# dualPilot.net
KiCad netlist of a schematic drawn in EAGLE
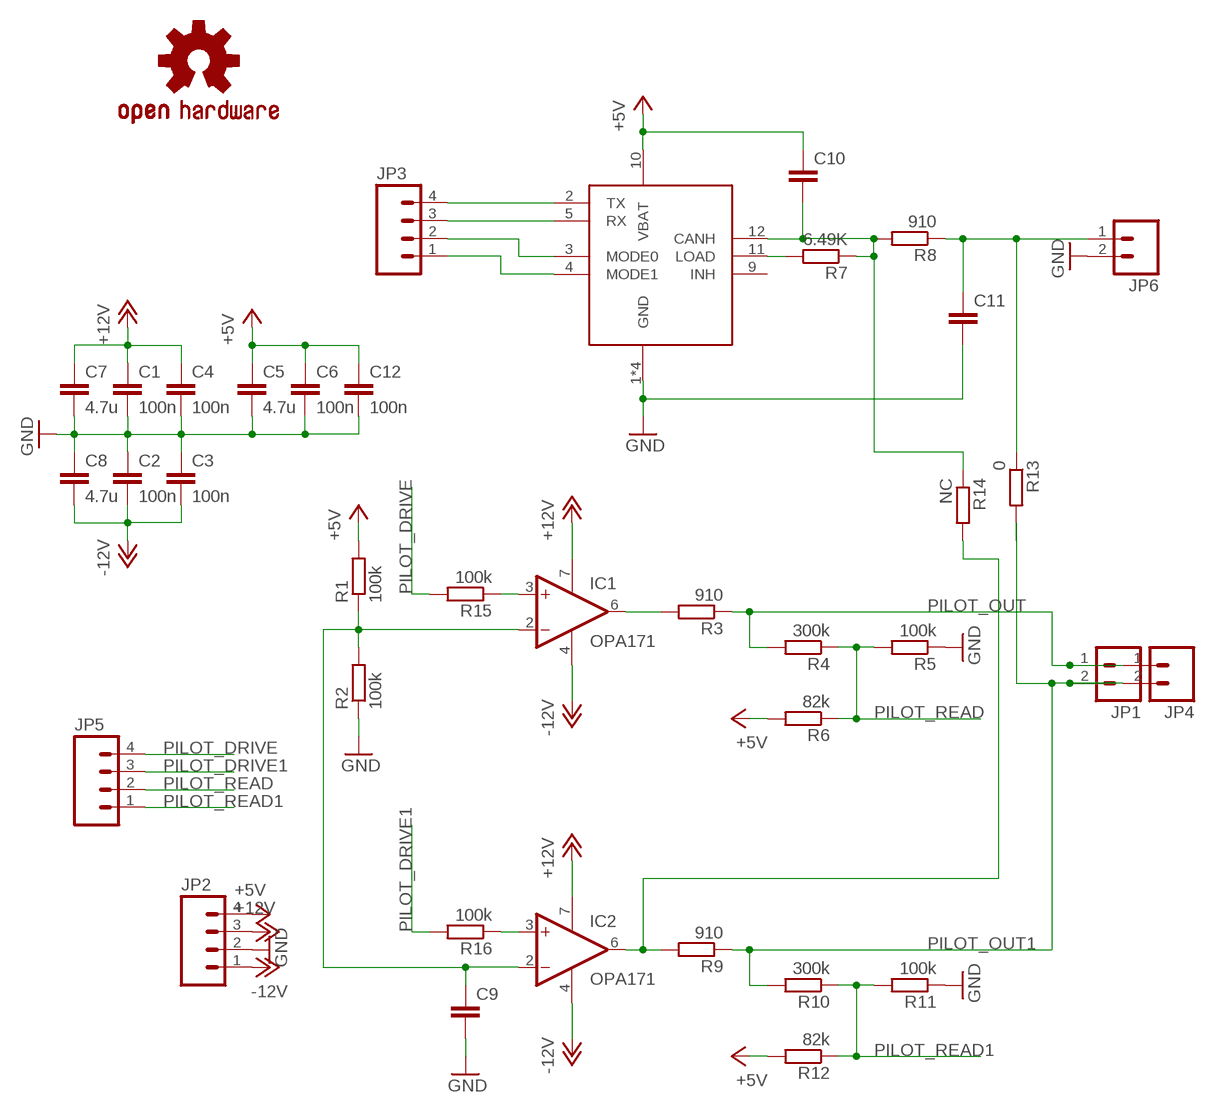
[diagram p0: schematic, sheet 1]

(export (version "E")
  (design (tool "Eeschema 10.0.6"))
  (components
    (comp (ref "C1")
      (value "100n")
      (footprint "eagle-import:0805")
      (libsource (lib "eagle-import") (part "CAP0805"))
    )
    (comp (ref "C2")
      (value "100n")
      (footprint "eagle-import:0805")
      (libsource (lib "eagle-import") (part "CAP0805"))
    )
    (comp (ref "C3")
      (value "100n")
      (footprint "eagle-import:0805")
      (libsource (lib "eagle-import") (part "CAP0805"))
    )
    (comp (ref "C4")
      (value "100n")
      (footprint "eagle-import:0805")
      (libsource (lib "eagle-import") (part "CAP0805"))
    )
    (comp (ref "C5")
      (value "4.7u")
      (footprint "eagle-import:0805")
      (libsource (lib "eagle-import") (part "CAP0805"))
    )
    (comp (ref "C6")
      (value "100n")
      (footprint "eagle-import:0805")
      (libsource (lib "eagle-import") (part "CAP0805"))
    )
    (comp (ref "C7")
      (value "4.7u")
      (footprint "eagle-import:0805")
      (libsource (lib "eagle-import") (part "CAP0805"))
    )
    (comp (ref "C8")
      (value "4.7u")
      (footprint "eagle-import:0805")
      (libsource (lib "eagle-import") (part "CAP0805"))
    )
    (comp (ref "C9")
      (value "CAP0805")
      (footprint "eagle-import:0805")
      (libsource (lib "eagle-import") (part "CAP0805"))
    )
    (comp (ref "C10")
      (value "CAP0805")
      (footprint "eagle-import:0805")
      (libsource (lib "eagle-import") (part "CAP0805"))
    )
    (comp (ref "C11")
      (value "CAP0805")
      (footprint "eagle-import:0805")
      (libsource (lib "eagle-import") (part "CAP0805"))
    )
    (comp (ref "C12")
      (value "100n")
      (footprint "eagle-import:0805")
      (libsource (lib "eagle-import") (part "CAP0805"))
    )
    (comp (ref "IC1")
      (value "OPA171")
      (footprint "eagle-import:SO08")
      (libsource (lib "eagle-import") (part "OPAU344"))
    )
    (comp (ref "IC2")
      (value "OPA171")
      (footprint "eagle-import:SO08")
      (libsource (lib "eagle-import") (part "OPAU344"))
    )
    (comp (ref "JP1")
      (value "M02LOCK_LONGPADS")
      (footprint "eagle-import:1X02_LOCK_LONGPADS")
      (libsource (lib "eagle-import") (part "M02LOCK_LONGPADS"))
    )
    (comp (ref "JP2")
      (value "M04LONGPADS")
      (footprint "eagle-import:1X04_LONGPADS")
      (libsource (lib "eagle-import") (part "M04LONGPADS"))
    )
    (comp (ref "JP3")
      (value "M04LONGPADS")
      (footprint "eagle-import:1X04_LONGPADS")
      (libsource (lib "eagle-import") (part "SparkFun-Connectors_M04LONGPADS"))
    )
    (comp (ref "JP4")
      (value "M025MM")
      (footprint "eagle-import:SCREWTERMINAL-5MM-2")
      (libsource (lib "eagle-import") (part "SparkFun-Connectors_M025MM"))
    )
    (comp (ref "JP5")
      (value "M04LONGPADS")
      (footprint "eagle-import:1X04_LONGPADS")
      (libsource (lib "eagle-import") (part "SparkFun-Connectors_M04LONGPADS"))
    )
    (comp (ref "JP6")
      (value "M02LOCK_LONGPADS")
      (footprint "eagle-import:1X02_LOCK_LONGPADS")
      (libsource (lib "eagle-import") (part "M02LOCK_LONGPADS"))
    )
    (comp (ref "R1")
      (value "100k")
      (footprint "eagle-import:R0805")
      (libsource (lib "eagle-import") (part "R-EU_R0805"))
    )
    (comp (ref "R2")
      (value "100k")
      (footprint "eagle-import:R0805")
      (libsource (lib "eagle-import") (part "R-EU_R0805"))
    )
    (comp (ref "R3")
      (value "910")
      (footprint "eagle-import:R1206")
      (libsource (lib "eagle-import") (part "R-EU_R1206"))
    )
    (comp (ref "R4")
      (value "300k")
      (footprint "eagle-import:R0805")
      (libsource (lib "eagle-import") (part "R-EU_R0805"))
    )
    (comp (ref "R5")
      (value "100k")
      (footprint "eagle-import:R0805")
      (libsource (lib "eagle-import") (part "R-EU_R0805"))
    )
    (comp (ref "R6")
      (value "82k")
      (footprint "eagle-import:R0805")
      (libsource (lib "eagle-import") (part "R-EU_R0805"))
    )
    (comp (ref "R7")
      (value "6.49K")
      (footprint "eagle-import:R0805")
      (libsource (lib "eagle-import") (part "R-EU_R0805"))
    )
    (comp (ref "R8")
      (value "910")
      (footprint "eagle-import:R1206")
      (libsource (lib "eagle-import") (part "R-EU_R1206"))
    )
    (comp (ref "R9")
      (value "910")
      (footprint "eagle-import:R1206")
      (libsource (lib "eagle-import") (part "R-EU_R1206"))
    )
    (comp (ref "R10")
      (value "300k")
      (footprint "eagle-import:R0805")
      (libsource (lib "eagle-import") (part "R-EU_R0805"))
    )
    (comp (ref "R11")
      (value "100k")
      (footprint "eagle-import:R0805")
      (libsource (lib "eagle-import") (part "R-EU_R0805"))
    )
    (comp (ref "R12")
      (value "82k")
      (footprint "eagle-import:R0805")
      (libsource (lib "eagle-import") (part "R-EU_R0805"))
    )
    (comp (ref "R13")
      (value "0")
      (footprint "eagle-import:R0805")
      (libsource (lib "eagle-import") (part "R-EU_R0805"))
    )
    (comp (ref "R14")
      (value "NC")
      (footprint "eagle-import:R0805")
      (libsource (lib "eagle-import") (part "R-EU_R0805"))
    )
    (comp (ref "R15")
      (value "100k")
      (footprint "eagle-import:R0805")
      (libsource (lib "eagle-import") (part "R-EU_R0805"))
    )
    (comp (ref "R16")
      (value "100k")
      (footprint "eagle-import:R0805")
      (libsource (lib "eagle-import") (part "R-EU_R0805"))
    )
    (comp (ref "U$1")
      (value "NCV7356")
      (footprint "eagle-import:SO14")
      (libsource (lib "eagle-import") (part "NCV7356"))
    )
    (comp (ref "U$2")
      (value "OSHW-LOGOS")
      (footprint "eagle-import:OSHW-LOGO-S")
      (libsource (lib "eagle-import") (part "OSHW-LOGOS"))
    )
  )
  (nets
    (net (code "1") (name "+5V") (class "Default")
      (node (ref "C10") (pin "1") (pinfunction "1_1") (pintype "passive"))
      (node (ref "C12") (pin "1") (pinfunction "1_1") (pintype "passive"))
      (node (ref "C5") (pin "1") (pinfunction "1_1") (pintype "passive"))
      (node (ref "C6") (pin "1") (pinfunction "1_1") (pintype "passive"))
      (node (ref "JP2") (pin "4") (pinfunction "4_4") (pintype "passive"))
      (node (ref "R1") (pin "2") (pinfunction "2_2") (pintype "passive"))
      (node (ref "R12") (pin "2") (pinfunction "2_2") (pintype "passive"))
      (node (ref "R6") (pin "2") (pinfunction "2_2") (pintype "passive"))
      (node (ref "U$1") (pin "10") (pinfunction "VBAT_10") (pintype "power_in"))
    )
    (net (code "2") (name "+12V") (class "Default")
      (node (ref "C1") (pin "1") (pinfunction "1_1") (pintype "passive"))
      (node (ref "C4") (pin "1") (pinfunction "1_1") (pintype "passive"))
      (node (ref "C7") (pin "1") (pinfunction "1_1") (pintype "passive"))
      (node (ref "IC1") (pin "7") (pinfunction "V+_7") (pintype "power_in"))
      (node (ref "IC2") (pin "7") (pinfunction "V+_7") (pintype "power_in"))
      (node (ref "JP2") (pin "3") (pinfunction "3_3") (pintype "passive"))
    )
    (net (code "3") (name "-12V") (class "Default")
      (node (ref "C2") (pin "2") (pinfunction "2_2") (pintype "passive"))
      (node (ref "C3") (pin "2") (pinfunction "2_2") (pintype "passive"))
      (node (ref "C8") (pin "2") (pinfunction "2_2") (pintype "passive"))
      (node (ref "IC1") (pin "4") (pinfunction "V-_4") (pintype "power_in"))
      (node (ref "IC2") (pin "4") (pinfunction "V-_4") (pintype "power_in"))
      (node (ref "JP2") (pin "1") (pinfunction "1_1") (pintype "passive"))
    )
    (net (code "4") (name "/PILOT_DRIVE") (class "Default")
      (node (ref "JP5") (pin "4") (pinfunction "4_4") (pintype "passive"))
      (node (ref "R15") (pin "2") (pinfunction "2_2") (pintype "passive"))
    )
    (net (code "5") (name "/PILOT_DRIVE1") (class "Default")
      (node (ref "JP5") (pin "3") (pinfunction "3_3") (pintype "passive"))
      (node (ref "R16") (pin "2") (pinfunction "2_2") (pintype "passive"))
    )
    (net (code "6") (name "/PILOT_OUT") (class "Default")
      (node (ref "JP1") (pin "1") (pinfunction "1_1") (pintype "passive"))
      (node (ref "JP4") (pin "1") (pinfunction "1_1") (pintype "passive"))
      (node (ref "R3") (pin "1") (pinfunction "1_1") (pintype "passive"))
      (node (ref "R4") (pin "2") (pinfunction "2_2") (pintype "passive"))
    )
    (net (code "7") (name "/PILOT_OUT1") (class "Default")
      (node (ref "JP1") (pin "2") (pinfunction "2_2") (pintype "passive"))
      (node (ref "JP4") (pin "2") (pinfunction "2_2") (pintype "passive"))
      (node (ref "R10") (pin "2") (pinfunction "2_2") (pintype "passive"))
      (node (ref "R13") (pin "2") (pinfunction "2_2") (pintype "passive"))
      (node (ref "R9") (pin "1") (pinfunction "1_1") (pintype "passive"))
    )
    (net (code "8") (name "/PILOT_READ") (class "Default")
      (node (ref "JP5") (pin "2") (pinfunction "2_2") (pintype "passive"))
      (node (ref "R4") (pin "1") (pinfunction "1_1") (pintype "passive"))
      (node (ref "R5") (pin "2") (pinfunction "2_2") (pintype "passive"))
      (node (ref "R6") (pin "1") (pinfunction "1_1") (pintype "passive"))
    )
    (net (code "9") (name "/PILOT_READ1") (class "Default")
      (node (ref "JP5") (pin "1") (pinfunction "1_1") (pintype "passive"))
      (node (ref "R10") (pin "1") (pinfunction "1_1") (pintype "passive"))
      (node (ref "R11") (pin "2") (pinfunction "2_2") (pintype "passive"))
      (node (ref "R12") (pin "1") (pinfunction "1_1") (pintype "passive"))
    )
    (net (code "10") (name "GND") (class "Default")
      (node (ref "C1") (pin "2") (pinfunction "2_2") (pintype "passive"))
      (node (ref "C11") (pin "2") (pinfunction "2_2") (pintype "passive"))
      (node (ref "C12") (pin "2") (pinfunction "2_2") (pintype "passive"))
      (node (ref "C2") (pin "1") (pinfunction "1_1") (pintype "passive"))
      (node (ref "C3") (pin "1") (pinfunction "1_1") (pintype "passive"))
      (node (ref "C4") (pin "2") (pinfunction "2_2") (pintype "passive"))
      (node (ref "C5") (pin "2") (pinfunction "2_2") (pintype "passive"))
      (node (ref "C6") (pin "2") (pinfunction "2_2") (pintype "passive"))
      (node (ref "C7") (pin "2") (pinfunction "2_2") (pintype "passive"))
      (node (ref "C8") (pin "1") (pinfunction "1_1") (pintype "passive"))
      (node (ref "C9") (pin "2") (pinfunction "2_2") (pintype "passive"))
      (node (ref "JP2") (pin "2") (pinfunction "2_2") (pintype "passive"))
      (node (ref "JP6") (pin "2") (pinfunction "2_2") (pintype "passive"))
      (node (ref "R11") (pin "1") (pinfunction "1_1") (pintype "passive"))
      (node (ref "R2") (pin "1") (pinfunction "1_1") (pintype "passive"))
      (node (ref "R5") (pin "1") (pinfunction "1_1") (pintype "passive"))
      (node (ref "U$1") (pin "1") (pinfunction "GND_1") (pintype "power_in"))
      (node (ref "U$1") (pin "14") (pinfunction "GND_14") (pintype "power_in"))
      (node (ref "U$1") (pin "7") (pinfunction "GND_7") (pintype "power_in"))
      (node (ref "U$1") (pin "8") (pinfunction "GND_8") (pintype "power_in"))
    )
    (net (code "11") (name "Net-(C11-Pad1)") (class "Default")
      (node (ref "C11") (pin "1") (pinfunction "1_1") (pintype "passive"))
      (node (ref "JP6") (pin "1") (pinfunction "1_1") (pintype "passive"))
      (node (ref "R13") (pin "1") (pinfunction "1_1") (pintype "passive"))
      (node (ref "R8") (pin "1") (pinfunction "1_1") (pintype "passive"))
    )
    (net (code "12") (name "Net-(IC1-+IN)") (class "Default")
      (node (ref "IC1") (pin "3") (pinfunction "+IN_3") (pintype "input"))
      (node (ref "R15") (pin "1") (pinfunction "1_1") (pintype "passive"))
    )
    (net (code "13") (name "Net-(IC1--IN)") (class "Default")
      (node (ref "C9") (pin "1") (pinfunction "1_1") (pintype "passive"))
      (node (ref "IC1") (pin "2") (pinfunction "-IN_2") (pintype "input"))
      (node (ref "IC2") (pin "2") (pinfunction "-IN_2") (pintype "input"))
      (node (ref "R1") (pin "1") (pinfunction "1_1") (pintype "passive"))
      (node (ref "R2") (pin "2") (pinfunction "2_2") (pintype "passive"))
    )
    (net (code "14") (name "Net-(IC1-OUT)") (class "Default")
      (node (ref "IC1") (pin "6") (pinfunction "OUT_6") (pintype "output"))
      (node (ref "R3") (pin "2") (pinfunction "2_2") (pintype "passive"))
    )
    (net (code "15") (name "Net-(IC2-+IN)") (class "Default")
      (node (ref "IC2") (pin "3") (pinfunction "+IN_3") (pintype "input"))
      (node (ref "R16") (pin "1") (pinfunction "1_1") (pintype "passive"))
    )
    (net (code "16") (name "Net-(IC2-OUT)") (class "Default")
      (node (ref "IC2") (pin "6") (pinfunction "OUT_6") (pintype "output"))
      (node (ref "R14") (pin "2") (pinfunction "2_2") (pintype "passive"))
      (node (ref "R9") (pin "2") (pinfunction "2_2") (pintype "passive"))
    )
    (net (code "17") (name "Net-(U$1-CANH)") (class "Default")
      (node (ref "C10") (pin "2") (pinfunction "2_2") (pintype "passive"))
      (node (ref "R14") (pin "1") (pinfunction "1_1") (pintype "passive"))
      (node (ref "R7") (pin "1") (pinfunction "1_1") (pintype "passive"))
      (node (ref "R8") (pin "2") (pinfunction "2_2") (pintype "passive"))
      (node (ref "U$1") (pin "12") (pinfunction "CANH_12") (pintype "bidirectional"))
    )
    (net (code "18") (name "Net-(U$1-LOAD)") (class "Default")
      (node (ref "R7") (pin "2") (pinfunction "2_2") (pintype "passive"))
      (node (ref "U$1") (pin "11") (pinfunction "LOAD_11") (pintype "bidirectional"))
    )
    (net (code "19") (name "Net-(U$1-MODE0)") (class "Default")
      (node (ref "JP3") (pin "2") (pinfunction "2_2") (pintype "passive"))
      (node (ref "U$1") (pin "3") (pinfunction "MODE0_3") (pintype "bidirectional"))
    )
    (net (code "20") (name "Net-(U$1-MODE1)") (class "Default")
      (node (ref "JP3") (pin "1") (pinfunction "1_1") (pintype "passive"))
      (node (ref "U$1") (pin "4") (pinfunction "MODE1_4") (pintype "bidirectional"))
    )
    (net (code "21") (name "Net-(U$1-RX)") (class "Default")
      (node (ref "JP3") (pin "3") (pinfunction "3_3") (pintype "passive"))
      (node (ref "U$1") (pin "5") (pinfunction "RX_5") (pintype "bidirectional"))
    )
    (net (code "22") (name "Net-(U$1-TX)") (class "Default")
      (node (ref "JP3") (pin "4") (pinfunction "4_4") (pintype "passive"))
      (node (ref "U$1") (pin "2") (pinfunction "TX_2") (pintype "bidirectional"))
    )
    (net (code "23") (name "unconnected-(U$1-INH-Pad9)") (class "Default")
      (node (ref "U$1") (pin "9") (pinfunction "INH_9") (pintype "bidirectional"))
    )
  )
)
